# Timer_555___LEVEL.net
KiCad netlist of a schematic drawn in Altium Designer
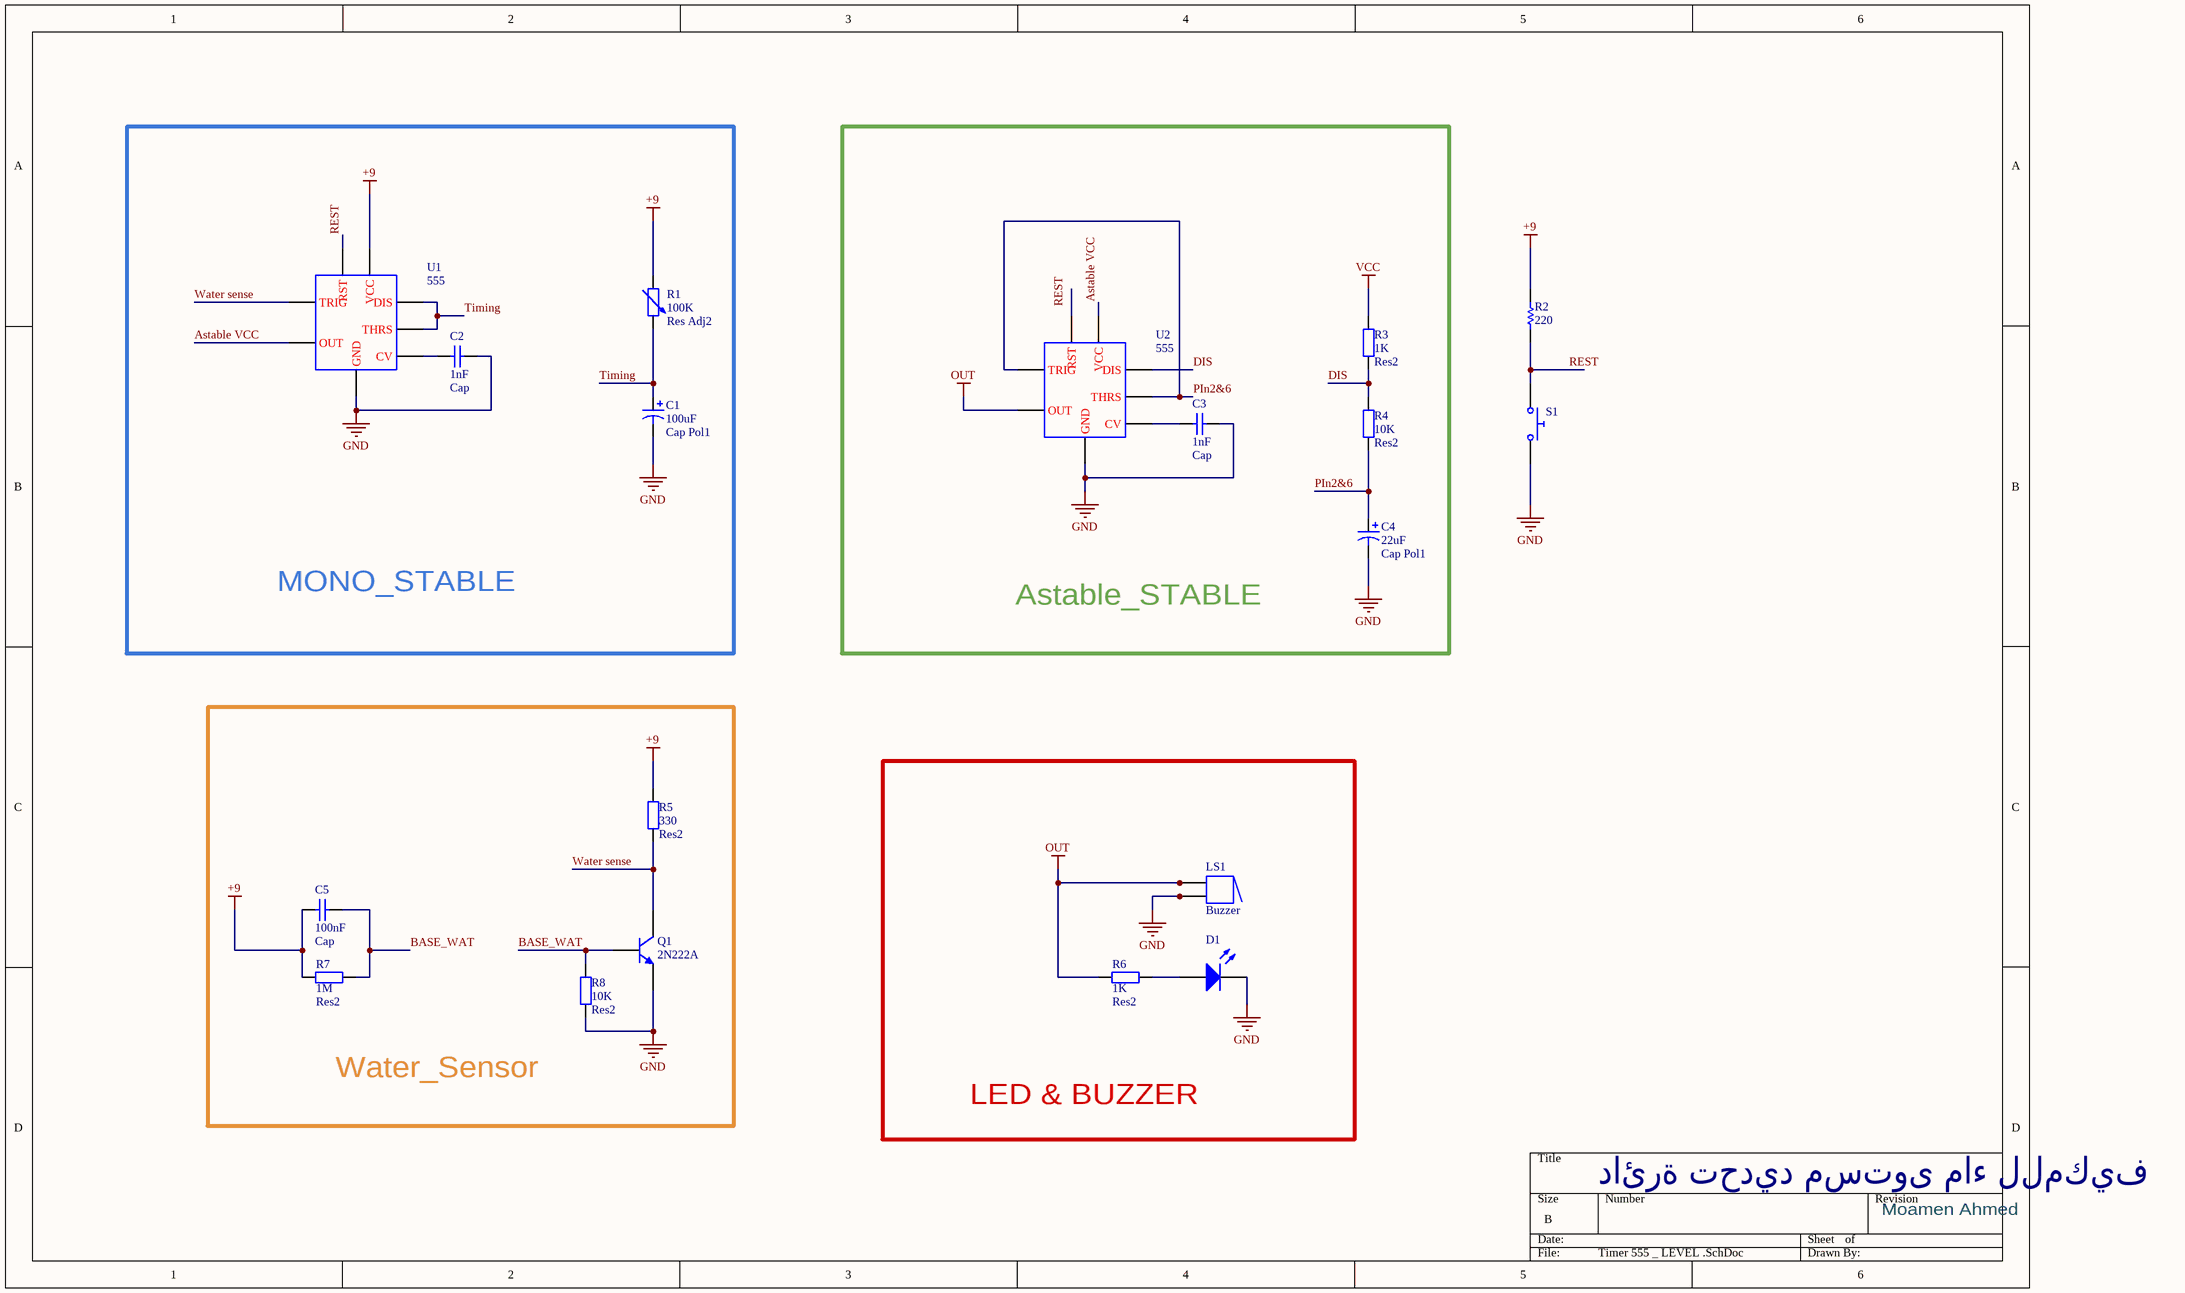
[diagram p0: Timer 555 _ LEVEL .SchDoc]

(export (version "E")
  (design (tool "Eeschema 10.0.6"))
  (components
    (comp (ref "C1")
      (value "Cap Pol1")
      (footprint "RB7.6-15")
      (description "Polarized Capacitor (Radial)")
      (fields (field (name "ALTIUM_VALUE") "100uF") (field (name "PUBLISHER") "Altium Limited"))
      (libsource (lib "Miscellaneous Devices") (part "Cap Pol1"))
    )
    (comp (ref "C2")
      (value "Cap")
      (footprint "RAD-0.3")
      (description "Capacitor")
      (fields (field (name "ALTIUM_VALUE") "1nF") (field (name "PUBLISHER") "Altium Limited"))
      (libsource (lib "Miscellaneous Devices") (part "Cap"))
    )
    (comp (ref "C3")
      (value "Cap")
      (footprint "RAD-0.3")
      (description "Capacitor")
      (fields (field (name "ALTIUM_VALUE") "1nF") (field (name "PUBLISHER") "Altium Limited"))
      (libsource (lib "Miscellaneous Devices") (part "Cap"))
    )
    (comp (ref "C4")
      (value "Cap Pol1")
      (footprint "RB7.6-15")
      (description "Polarized Capacitor (Radial)")
      (fields (field (name "ALTIUM_VALUE") "22uF") (field (name "PUBLISHER") "Altium Limited"))
      (libsource (lib "Miscellaneous Devices") (part "Cap Pol1"))
    )
    (comp (ref "C5")
      (value "Cap")
      (footprint "RAD-0.3")
      (description "Capacitor")
      (fields (field (name "ALTIUM_VALUE") "100nF") (field (name "PUBLISHER") "Altium Limited"))
      (libsource (lib "Miscellaneous Devices") (part "Cap"))
    )
    (comp (ref "D1")
      (value "Light-Emitting Diode")
      (libsource (lib "Simulation Generic Components") (part "LED"))
    )
    (comp (ref "LS1")
      (value "Buzzer")
      (footprint "ABSM-1574")
      (description "Magnetic Transducer Buzzer")
      (fields (field (name "PUBLISHER") "Altium Limited"))
      (libsource (lib "Miscellaneous Devices") (part "Buzzer"))
    )
    (comp (ref "Q1")
      (value "2N222A")
      (footprint "TO-92A")
      (description "NPN General Purpose Amplifier")
      (fields (field (name "PUBLISHER") "Altium Limited"))
      (libsource (lib "Miscellaneous Devices") (part "2N3904"))
    )
    (comp (ref "R1")
      (value "Res Adj2")
      (footprint "AXIAL-0.6")
      (description "Variable Resistor")
      (fields (field (name "ALTIUM_VALUE") "100K") (field (name "PUBLISHER") "Altium Limited"))
      (libsource (lib "Miscellaneous Devices") (part "Res Adj2"))
    )
    (comp (ref "R2")
      (value "220")
      (description "Resistor")
      (libsource (lib "Simulation Generic Components") (part "Resistor"))
    )
    (comp (ref "R3")
      (value "Res2")
      (footprint "AXIAL-0.4")
      (description "Resistor")
      (fields (field (name "ALTIUM_VALUE") "1K") (field (name "PUBLISHER") "Altium Limited"))
      (libsource (lib "") (part "Res2_1"))
    )
    (comp (ref "R4")
      (value "Res2")
      (footprint "AXIAL-0.4")
      (description "Resistor")
      (fields (field (name "ALTIUM_VALUE") "10K") (field (name "PUBLISHER") "Altium Limited"))
      (libsource (lib "") (part "Res2_1"))
    )
    (comp (ref "R5")
      (value "Res2")
      (footprint "AXIAL-0.4")
      (description "Resistor")
      (fields (field (name "ALTIUM_VALUE") "330") (field (name "PUBLISHER") "Altium Limited"))
      (libsource (lib "") (part "Res2_1"))
    )
    (comp (ref "R6")
      (value "Res2")
      (footprint "AXIAL-0.4")
      (description "Resistor")
      (fields (field (name "ALTIUM_VALUE") "1K") (field (name "PUBLISHER") "Altium Limited"))
      (libsource (lib "Miscellaneous Devices") (part "Res2"))
    )
    (comp (ref "R7")
      (value "Res2")
      (footprint "AXIAL-0.4")
      (description "Resistor")
      (fields (field (name "ALTIUM_VALUE") "1M") (field (name "PUBLISHER") "Altium Limited"))
      (libsource (lib "Miscellaneous Devices") (part "Res2"))
    )
    (comp (ref "R8")
      (value "Res2")
      (footprint "AXIAL-0.4")
      (description "Resistor")
      (fields (field (name "ALTIUM_VALUE") "10K") (field (name "PUBLISHER") "Altium Limited"))
      (libsource (lib "") (part "Res2_1"))
    )
    (comp (ref "S1")
      (value "Push Button Normally Opened")
      (libsource (lib "Simulation Generic Components") (part "Push Button NO"))
    )
    (comp (ref "U1")
      (value "555")
      (description "Timer 555")
      (libsource (lib "Simulation Generic Components") (part "555"))
    )
    (comp (ref "U2")
      (value "555")
      (description "Timer 555")
      (libsource (lib "Simulation Generic Components") (part "555"))
    )
  )
  (nets
    (net (code "1") (name "+9") (class "Default")
      (node (ref "C5") (pin "1") (pinfunction "1_1") (pintype "passive"))
      (node (ref "R1") (pin "1") (pinfunction "1_1") (pintype "passive"))
      (node (ref "R2") (pin "2") (pinfunction "2_2") (pintype "passive"))
      (node (ref "R5") (pin "2") (pinfunction "2_2") (pintype "passive"))
      (node (ref "R7") (pin "2") (pinfunction "2_2") (pintype "passive"))
      (node (ref "U1") (pin "8") (pinfunction "VCC_8") (pintype "passive"))
    )
    (net (code "2") (name "/Astable VCC") (class "Default")
      (node (ref "U1") (pin "3") (pinfunction "OUT_3") (pintype "passive"))
      (node (ref "U2") (pin "8") (pinfunction "VCC_8") (pintype "passive"))
    )
    (net (code "3") (name "/BASE_WAT") (class "Default")
      (node (ref "C5") (pin "2") (pinfunction "2_2") (pintype "passive"))
      (node (ref "Q1") (pin "2") (pinfunction "B_2") (pintype "passive"))
      (node (ref "R7") (pin "1") (pinfunction "1_1") (pintype "passive"))
      (node (ref "R8") (pin "2") (pinfunction "2_2") (pintype "passive"))
    )
    (net (code "4") (name "/DIS") (class "Default")
      (node (ref "R3") (pin "1") (pinfunction "1_1") (pintype "passive"))
      (node (ref "R4") (pin "2") (pinfunction "2_2") (pintype "passive"))
      (node (ref "U2") (pin "7") (pinfunction "DIS_7") (pintype "passive"))
    )
    (net (code "5") (name "/PIn2&6") (class "Default")
      (node (ref "C4") (pin "1") (pinfunction "1_1") (pintype "passive"))
      (node (ref "R4") (pin "1") (pinfunction "1_1") (pintype "passive"))
      (node (ref "U2") (pin "2") (pinfunction "TRIG_2") (pintype "passive"))
      (node (ref "U2") (pin "6") (pinfunction "THRS_6") (pintype "passive"))
    )
    (net (code "6") (name "/REST") (class "Default")
      (node (ref "R2") (pin "1") (pinfunction "1_1") (pintype "passive"))
      (node (ref "S1") (pin "1") (pinfunction "1_1") (pintype "passive"))
      (node (ref "U1") (pin "4") (pinfunction "RST_4") (pintype "passive"))
    )
    (net (code "7") (name "/Timing") (class "Default")
      (node (ref "C1") (pin "1") (pinfunction "1_1") (pintype "passive"))
      (node (ref "R1") (pin "2") (pinfunction "2_2") (pintype "passive"))
      (node (ref "U1") (pin "6") (pinfunction "THRS_6") (pintype "passive"))
      (node (ref "U1") (pin "7") (pinfunction "DIS_7") (pintype "passive"))
    )
    (net (code "8") (name "/Water sense") (class "Default")
      (node (ref "Q1") (pin "3") (pinfunction "C_3") (pintype "passive"))
      (node (ref "R5") (pin "1") (pinfunction "1_1") (pintype "passive"))
      (node (ref "U1") (pin "2") (pinfunction "TRIG_2") (pintype "passive"))
    )
    (net (code "9") (name "GND") (class "Default")
      (node (ref "C1") (pin "2") (pinfunction "2_2") (pintype "passive"))
      (node (ref "C2") (pin "2") (pinfunction "2_2") (pintype "passive"))
      (node (ref "C3") (pin "2") (pinfunction "2_2") (pintype "passive"))
      (node (ref "C4") (pin "2") (pinfunction "2_2") (pintype "passive"))
      (node (ref "D1") (pin "2") (pinfunction "K_2") (pintype "passive"))
      (node (ref "LS1") (pin "2") (pinfunction "2_2") (pintype "passive"))
      (node (ref "LS1") (pin "2A") (pinfunction "2A_2A") (pintype "passive"))
      (node (ref "Q1") (pin "1") (pinfunction "E_1") (pintype "passive"))
      (node (ref "R8") (pin "1") (pinfunction "1_1") (pintype "passive"))
      (node (ref "S1") (pin "2") (pinfunction "2_2") (pintype "passive"))
      (node (ref "U1") (pin "1") (pinfunction "GND_1") (pintype "passive"))
      (node (ref "U2") (pin "1") (pinfunction "GND_1") (pintype "passive"))
    )
    (net (code "10") (name "Net-(D1-A)") (class "Default")
      (node (ref "D1") (pin "1") (pinfunction "A_1") (pintype "passive"))
      (node (ref "R6") (pin "1") (pinfunction "1_1") (pintype "passive"))
    )
    (net (code "11") (name "Net-(U1-CV)") (class "Default")
      (node (ref "C2") (pin "1") (pinfunction "1_1") (pintype "passive"))
      (node (ref "U1") (pin "5") (pinfunction "CV_5") (pintype "passive"))
    )
    (net (code "12") (name "Net-(U2-CV)") (class "Default")
      (node (ref "C3") (pin "1") (pinfunction "1_1") (pintype "passive"))
      (node (ref "U2") (pin "5") (pinfunction "CV_5") (pintype "passive"))
    )
    (net (code "13") (name "OUT") (class "Default")
      (node (ref "LS1") (pin "1") (pinfunction "1_1") (pintype "passive"))
      (node (ref "LS1") (pin "1A") (pinfunction "1A_1A") (pintype "passive"))
      (node (ref "R6") (pin "2") (pinfunction "2_2") (pintype "passive"))
      (node (ref "U2") (pin "3") (pinfunction "OUT_3") (pintype "passive"))
    )
    (net (code "14") (name "VCC") (class "Default")
      (node (ref "R3") (pin "2") (pinfunction "2_2") (pintype "passive"))
    )
    (net (code "15") (name "unconnected-(U2-RST-Pad4)") (class "Default")
      (node (ref "U2") (pin "4") (pinfunction "RST_4") (pintype "passive"))
    )
  )
)
